# ShieldKL25zG18.net
KiCad netlist of a schematic drawn in Altium Designer
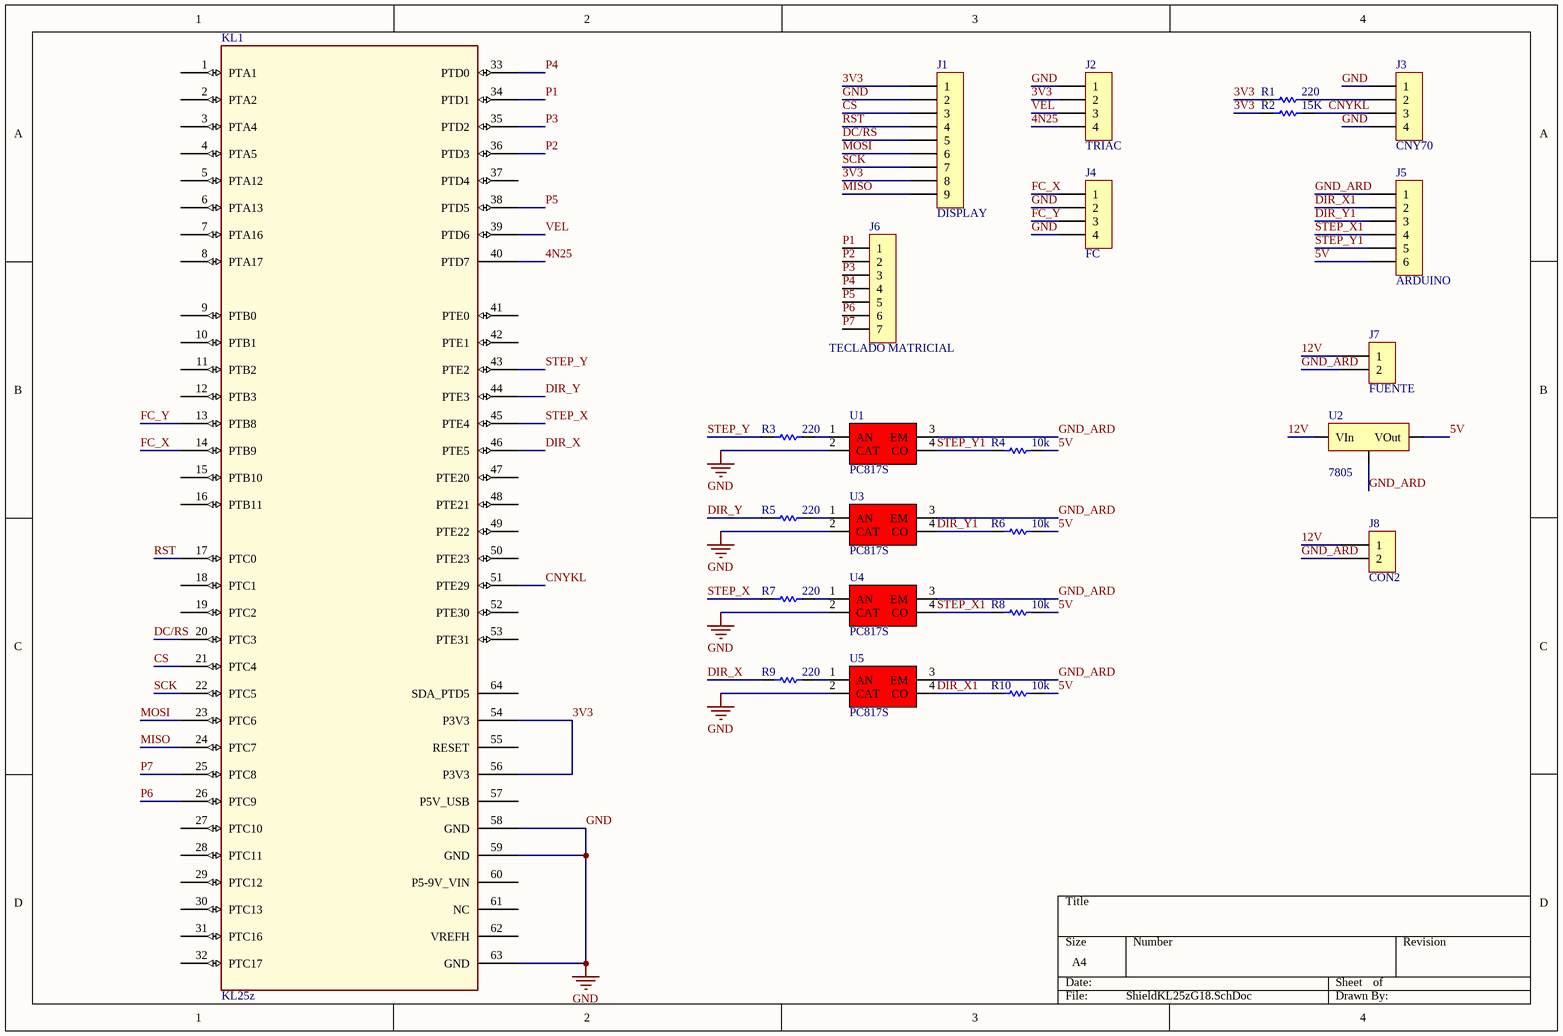
[diagram p0: ShieldKL25zG18.SchDoc]

(export (version "E")
  (design (tool "Eeschema 10.0.6"))
  (components
    (comp (ref "J1") (value "DISPLAY") (footprint "SIP9") (libsource (lib "LIBEBAL") (part "CON9")))
    (comp (ref "J2") (value "TRIAC") (footprint "SIP4") (libsource (lib "ShieldKL25zG18") (part "CON4")))
    (comp (ref "J3") (value "CNY70") (footprint "SIP4") (libsource (lib "Schlib1") (part "CON4")))
    (comp (ref "J4") (value "FC") (footprint "SIP4") (libsource (lib "ShieldKL25zG18") (part "CON4")))
    (comp (ref "J5") (value "ARDUINO") (footprint "SIP6") (libsource (lib "5A_BRULA,Tomas") (part "CON6")))
    (comp (ref "J6")
      (value "TECLADO MATRICIAL")
      (footprint "SIP7")
      (libsource (lib "5A_BRULA,Tomas") (part "CON7"))
    )
    (comp (ref "J7") (value "FUENTE") (footprint "BORNERA2") (libsource (lib "LIBEBAL") (part "BORNERA 2")))
    (comp (ref "J8") (value "CON2") (footprint "SIP2") (libsource (lib "5A_BRULA,Tomas") (part "CON2")))
    (comp (ref "KL1")
      (value "KL25z")
      (footprint "Freedom KL25Z Headerarray")
      (libsource (lib "ShieldKL25zG18") (part "KL25z"))
    )
    (comp (ref "R1") (value "220") (footprint "0805") (libsource (lib "5A_BRULA,Tomas") (part "RES")))
    (comp (ref "R2") (value "15K") (footprint "0805") (libsource (lib "LIBEBAL") (part "RES")))
    (comp (ref "R3") (value "220") (footprint "0805") (libsource (lib "5A_BRULA,Tomas") (part "RES")))
    (comp (ref "R4") (value "10k") (footprint "0805") (libsource (lib "5A_BRULA,Tomas") (part "RES")))
    (comp (ref "R5") (value "220") (footprint "0805") (libsource (lib "5A_BRULA,Tomas") (part "RES")))
    (comp (ref "R6") (value "10k") (footprint "0805") (libsource (lib "5A_BRULA,Tomas") (part "RES")))
    (comp (ref "R7") (value "220") (footprint "0805") (libsource (lib "5A_BRULA,Tomas") (part "RES")))
    (comp (ref "R8") (value "10k") (footprint "0805") (libsource (lib "5A_BRULA,Tomas") (part "RES")))
    (comp (ref "R9") (value "220") (footprint "0805") (libsource (lib "5A_BRULA,Tomas") (part "RES")))
    (comp (ref "R10") (value "10k") (footprint "0805") (libsource (lib "5A_BRULA,Tomas") (part "RES")))
    (comp (ref "U1")
      (value "PC817S")
      (footprint "OPTO_SMD")
      (libsource (lib "5A_BRULA,Tomas") (part "OPTO_SMD"))
    )
    (comp (ref "U2")
      (value "7805")
      (footprint "TO-220 V")
      (description "REGULDOR POSITIVO")
      (libsource (lib "LIBEBAL") (part "78XX"))
    )
    (comp (ref "U3")
      (value "PC817S")
      (footprint "OPTO_SMD")
      (libsource (lib "5A_BRULA,Tomas") (part "OPTO_SMD"))
    )
    (comp (ref "U4")
      (value "PC817S")
      (footprint "OPTO_SMD")
      (libsource (lib "5A_BRULA,Tomas") (part "OPTO_SMD"))
    )
    (comp (ref "U5")
      (value "PC817S")
      (footprint "OPTO_SMD")
      (libsource (lib "5A_BRULA,Tomas") (part "OPTO_SMD"))
    )
  )
  (nets
    (net (code "1") (name "/3V3") (class "Default")
      (node (ref "J1") (pin "1") (pinfunction "1_1") (pintype "passive"))
      (node (ref "J1") (pin "8") (pinfunction "8_8") (pintype "passive"))
      (node (ref "J2") (pin "2") (pinfunction "2_2") (pintype "passive"))
      (node (ref "KL1") (pin "54") (pinfunction "P3V3_54") (pintype "power_in"))
      (node (ref "KL1") (pin "56") (pinfunction "P3V3_56") (pintype "power_in"))
      (node (ref "R1") (pin "1") (pinfunction "1_1") (pintype "passive"))
      (node (ref "R2") (pin "2") (pinfunction "2_2") (pintype "passive"))
    )
    (net (code "2") (name "/4N25") (class "Default")
      (node (ref "J2") (pin "4") (pinfunction "4_4") (pintype "passive"))
      (node (ref "KL1") (pin "40") (pinfunction "PTD7_40") (pintype "passive"))
    )
    (net (code "3") (name "/5V") (class "Default")
      (node (ref "J5") (pin "6") (pinfunction "6_6") (pintype "passive"))
      (node (ref "R10") (pin "2") (pinfunction "2_2") (pintype "passive"))
      (node (ref "R4") (pin "2") (pinfunction "2_2") (pintype "passive"))
      (node (ref "R6") (pin "2") (pinfunction "2_2") (pintype "passive"))
      (node (ref "R8") (pin "2") (pinfunction "2_2") (pintype "passive"))
      (node (ref "U2") (pin "3") (pinfunction "VOut_3") (pintype "passive"))
    )
    (net (code "4") (name "/12V") (class "Default")
      (node (ref "J7") (pin "1") (pinfunction "1_1") (pintype "passive"))
      (node (ref "J8") (pin "1") (pinfunction "1_1") (pintype "passive"))
      (node (ref "U2") (pin "1") (pinfunction "VIn_1") (pintype "passive"))
    )
    (net (code "6") (name "/CNYKL") (class "Default")
      (node (ref "J3") (pin "3") (pinfunction "3_3") (pintype "passive"))
      (node (ref "KL1") (pin "51") (pinfunction "PTE29_51") (pintype "bidirectional"))
      (node (ref "R2") (pin "1") (pinfunction "1_1") (pintype "passive"))
    )
    (net (code "7") (name "/CS") (class "Default")
      (node (ref "J1") (pin "3") (pinfunction "3_3") (pintype "passive"))
      (node (ref "KL1") (pin "21") (pinfunction "PTC4_21") (pintype "bidirectional"))
    )
    (net (code "8") (name "/DC{slash}RS") (class "Default")
      (node (ref "J1") (pin "5") (pinfunction "5_5") (pintype "passive"))
      (node (ref "KL1") (pin "20") (pinfunction "PTC3_20") (pintype "bidirectional"))
    )
    (net (code "9") (name "/DIR_X") (class "Default")
      (node (ref "KL1") (pin "46") (pinfunction "PTE5_46") (pintype "bidirectional"))
      (node (ref "R9") (pin "1") (pinfunction "1_1") (pintype "passive"))
    )
    (net (code "10") (name "/DIR_X1") (class "Default")
      (node (ref "J5") (pin "2") (pinfunction "2_2") (pintype "passive"))
      (node (ref "R10") (pin "1") (pinfunction "1_1") (pintype "passive"))
      (node (ref "U5") (pin "4") (pinfunction "CO_4") (pintype "passive"))
    )
    (net (code "11") (name "/DIR_Y") (class "Default")
      (node (ref "KL1") (pin "44") (pinfunction "PTE3_44") (pintype "bidirectional"))
      (node (ref "R5") (pin "1") (pinfunction "1_1") (pintype "passive"))
    )
    (net (code "12") (name "/DIR_Y1") (class "Default")
      (node (ref "J5") (pin "3") (pinfunction "3_3") (pintype "passive"))
      (node (ref "R6") (pin "1") (pinfunction "1_1") (pintype "passive"))
      (node (ref "U3") (pin "4") (pinfunction "CO_4") (pintype "passive"))
    )
    (net (code "13") (name "/FC_X") (class "Default")
      (node (ref "J4") (pin "1") (pinfunction "1_1") (pintype "passive"))
      (node (ref "KL1") (pin "14") (pinfunction "PTB9_14") (pintype "bidirectional"))
    )
    (net (code "14") (name "/FC_Y") (class "Default")
      (node (ref "J4") (pin "3") (pinfunction "3_3") (pintype "passive"))
      (node (ref "KL1") (pin "13") (pinfunction "PTB8_13") (pintype "bidirectional"))
    )
    (net (code "15") (name "/GND_ARD") (class "Default")
      (node (ref "J5") (pin "1") (pinfunction "1_1") (pintype "passive"))
      (node (ref "J7") (pin "2") (pinfunction "2_2") (pintype "passive"))
      (node (ref "J8") (pin "2") (pinfunction "2_2") (pintype "passive"))
      (node (ref "U1") (pin "3") (pinfunction "EM_3") (pintype "passive"))
      (node (ref "U2") (pin "2") (pinfunction "GND_2") (pintype "passive"))
      (node (ref "U3") (pin "3") (pinfunction "EM_3") (pintype "passive"))
      (node (ref "U4") (pin "3") (pinfunction "EM_3") (pintype "passive"))
      (node (ref "U5") (pin "3") (pinfunction "EM_3") (pintype "passive"))
    )
    (net (code "16") (name "/MISO") (class "Default")
      (node (ref "J1") (pin "9") (pinfunction "9_9") (pintype "passive"))
      (node (ref "KL1") (pin "24") (pinfunction "PTC7_24") (pintype "bidirectional"))
    )
    (net (code "17") (name "/MOSI") (class "Default")
      (node (ref "J1") (pin "6") (pinfunction "6_6") (pintype "passive"))
      (node (ref "KL1") (pin "23") (pinfunction "PTC6_23") (pintype "bidirectional"))
    )
    (net (code "18") (name "/P1") (class "Default")
      (node (ref "J6") (pin "1") (pinfunction "1_1") (pintype "passive"))
      (node (ref "KL1") (pin "34") (pinfunction "PTD1_34") (pintype "bidirectional"))
    )
    (net (code "19") (name "/P2") (class "Default")
      (node (ref "J6") (pin "2") (pinfunction "2_2") (pintype "passive"))
      (node (ref "KL1") (pin "36") (pinfunction "PTD3_36") (pintype "bidirectional"))
    )
    (net (code "20") (name "/P3") (class "Default")
      (node (ref "J6") (pin "3") (pinfunction "3_3") (pintype "passive"))
      (node (ref "KL1") (pin "35") (pinfunction "PTD2_35") (pintype "bidirectional"))
    )
    (net (code "21") (name "/P4") (class "Default")
      (node (ref "J6") (pin "4") (pinfunction "4_4") (pintype "passive"))
      (node (ref "KL1") (pin "33") (pinfunction "PTD0_33") (pintype "bidirectional"))
    )
    (net (code "22") (name "/P5") (class "Default")
      (node (ref "J6") (pin "5") (pinfunction "5_5") (pintype "passive"))
      (node (ref "KL1") (pin "38") (pinfunction "PTD5_38") (pintype "bidirectional"))
    )
    (net (code "23") (name "/P6") (class "Default")
      (node (ref "J6") (pin "6") (pinfunction "6_6") (pintype "passive"))
      (node (ref "KL1") (pin "26") (pinfunction "PTC9_26") (pintype "bidirectional"))
    )
    (net (code "24") (name "/P7") (class "Default")
      (node (ref "J6") (pin "7") (pinfunction "7_7") (pintype "passive"))
      (node (ref "KL1") (pin "25") (pinfunction "PTC8_25") (pintype "bidirectional"))
    )
    (net (code "25") (name "/RST") (class "Default")
      (node (ref "J1") (pin "4") (pinfunction "4_4") (pintype "passive"))
      (node (ref "KL1") (pin "17") (pinfunction "PTC0_17") (pintype "bidirectional"))
    )
    (net (code "26") (name "/SCK") (class "Default")
      (node (ref "J1") (pin "7") (pinfunction "7_7") (pintype "passive"))
      (node (ref "KL1") (pin "22") (pinfunction "PTC5_22") (pintype "bidirectional"))
    )
    (net (code "27") (name "/STEP_X") (class "Default")
      (node (ref "KL1") (pin "45") (pinfunction "PTE4_45") (pintype "bidirectional"))
      (node (ref "R7") (pin "1") (pinfunction "1_1") (pintype "passive"))
    )
    (net (code "28") (name "/STEP_X1") (class "Default")
      (node (ref "J5") (pin "4") (pinfunction "4_4") (pintype "passive"))
      (node (ref "R8") (pin "1") (pinfunction "1_1") (pintype "passive"))
      (node (ref "U4") (pin "4") (pinfunction "CO_4") (pintype "passive"))
    )
    (net (code "29") (name "/STEP_Y") (class "Default")
      (node (ref "KL1") (pin "43") (pinfunction "PTE2_43") (pintype "bidirectional"))
      (node (ref "R3") (pin "1") (pinfunction "1_1") (pintype "passive"))
    )
    (net (code "30") (name "/STEP_Y1") (class "Default")
      (node (ref "J5") (pin "5") (pinfunction "5_5") (pintype "passive"))
      (node (ref "R4") (pin "1") (pinfunction "1_1") (pintype "passive"))
      (node (ref "U1") (pin "4") (pinfunction "CO_4") (pintype "passive"))
    )
    (net (code "31") (name "/VEL") (class "Default")
      (node (ref "J2") (pin "3") (pinfunction "3_3") (pintype "passive"))
      (node (ref "KL1") (pin "39") (pinfunction "PTD6_39") (pintype "bidirectional"))
    )
    (net (code "32") (name "GND") (class "Default")
      (node (ref "J1") (pin "2") (pinfunction "2_2") (pintype "passive"))
      (node (ref "J2") (pin "1") (pinfunction "1_1") (pintype "passive"))
      (node (ref "J3") (pin "1") (pinfunction "1_1") (pintype "passive"))
      (node (ref "J3") (pin "4") (pinfunction "4_4") (pintype "passive"))
      (node (ref "J4") (pin "2") (pinfunction "2_2") (pintype "passive"))
      (node (ref "J4") (pin "4") (pinfunction "4_4") (pintype "passive"))
      (node (ref "KL1") (pin "58") (pinfunction "GND_58") (pintype "power_in"))
      (node (ref "KL1") (pin "59") (pinfunction "GND_59") (pintype "power_in"))
      (node (ref "KL1") (pin "63") (pinfunction "GND_63") (pintype "power_in"))
      (node (ref "U1") (pin "2") (pinfunction "CAT_2") (pintype "passive"))
      (node (ref "U3") (pin "2") (pinfunction "CAT_2") (pintype "passive"))
      (node (ref "U4") (pin "2") (pinfunction "CAT_2") (pintype "passive"))
      (node (ref "U5") (pin "2") (pinfunction "CAT_2") (pintype "passive"))
    )
    (net (code "33") (name "Net-(J3-Pad2)") (class "Default")
      (node (ref "J3") (pin "2") (pinfunction "2_2") (pintype "passive"))
      (node (ref "R1") (pin "2") (pinfunction "2_2") (pintype "passive"))
    )
    (net (code "34") (name "Net-(U1-AN)") (class "Default")
      (node (ref "R3") (pin "2") (pinfunction "2_2") (pintype "passive"))
      (node (ref "U1") (pin "1") (pinfunction "AN_1") (pintype "passive"))
    )
    (net (code "35") (name "Net-(U3-AN)") (class "Default")
      (node (ref "R5") (pin "2") (pinfunction "2_2") (pintype "passive"))
      (node (ref "U3") (pin "1") (pinfunction "AN_1") (pintype "passive"))
    )
    (net (code "36") (name "Net-(U4-AN)") (class "Default")
      (node (ref "R7") (pin "2") (pinfunction "2_2") (pintype "passive"))
      (node (ref "U4") (pin "1") (pinfunction "AN_1") (pintype "passive"))
    )
    (net (code "37") (name "Net-(U5-AN)") (class "Default")
      (node (ref "R9") (pin "2") (pinfunction "2_2") (pintype "passive"))
      (node (ref "U5") (pin "1") (pinfunction "AN_1") (pintype "passive"))
    )
    (net (code "38") (name "unconnected-(KL1-NC-Pad61)") (class "Default")
      (node (ref "KL1") (pin "61") (pinfunction "NC_61") (pintype "passive"))
    )
    (net (code "39") (name "unconnected-(KL1-P5-9V_VIN-Pad60)") (class "Default")
      (node (ref "KL1") (pin "60") (pinfunction "P5-9V_VIN_60") (pintype "passive"))
    )
    (net (code "40") (name "unconnected-(KL1-P5V_USB-Pad57)") (class "Default")
      (node (ref "KL1") (pin "57") (pinfunction "P5V_USB_57") (pintype "passive"))
    )
    (net (code "41") (name "unconnected-(KL1-PTA1-Pad1)") (class "Default")
      (node (ref "KL1") (pin "1") (pinfunction "PTA1_1") (pintype "bidirectional"))
    )
    (net (code "42") (name "unconnected-(KL1-PTA2-Pad2)") (class "Default")
      (node (ref "KL1") (pin "2") (pinfunction "PTA2_2") (pintype "bidirectional"))
    )
    (net (code "43") (name "unconnected-(KL1-PTA4-Pad3)") (class "Default")
      (node (ref "KL1") (pin "3") (pinfunction "PTA4_3") (pintype "bidirectional"))
    )
    (net (code "44") (name "unconnected-(KL1-PTA5-Pad4)") (class "Default")
      (node (ref "KL1") (pin "4") (pinfunction "PTA5_4") (pintype "bidirectional"))
    )
    (net (code "45") (name "unconnected-(KL1-PTA12-Pad5)") (class "Default")
      (node (ref "KL1") (pin "5") (pinfunction "PTA12_5") (pintype "bidirectional"))
    )
    (net (code "46") (name "unconnected-(KL1-PTA13-Pad6)") (class "Default")
      (node (ref "KL1") (pin "6") (pinfunction "PTA13_6") (pintype "bidirectional"))
    )
    (net (code "47") (name "unconnected-(KL1-PTA16-Pad7)") (class "Default")
      (node (ref "KL1") (pin "7") (pinfunction "PTA16_7") (pintype "bidirectional"))
    )
    (net (code "48") (name "unconnected-(KL1-PTA17-Pad8)") (class "Default")
      (node (ref "KL1") (pin "8") (pinfunction "PTA17_8") (pintype "bidirectional"))
    )
    (net (code "49") (name "unconnected-(KL1-PTB0-Pad9)") (class "Default")
      (node (ref "KL1") (pin "9") (pinfunction "PTB0_9") (pintype "bidirectional"))
    )
    (net (code "50") (name "unconnected-(KL1-PTB1-Pad10)") (class "Default")
      (node (ref "KL1") (pin "10") (pinfunction "PTB1_10") (pintype "bidirectional"))
    )
    (net (code "51") (name "unconnected-(KL1-PTB2-Pad11)") (class "Default")
      (node (ref "KL1") (pin "11") (pinfunction "PTB2_11") (pintype "bidirectional"))
    )
    (net (code "52") (name "unconnected-(KL1-PTB3-Pad12)") (class "Default")
      (node (ref "KL1") (pin "12") (pinfunction "PTB3_12") (pintype "bidirectional"))
    )
    (net (code "53") (name "unconnected-(KL1-PTB10-Pad15)") (class "Default")
      (node (ref "KL1") (pin "15") (pinfunction "PTB10_15") (pintype "bidirectional"))
    )
    (net (code "54") (name "unconnected-(KL1-PTB11-Pad16)") (class "Default")
      (node (ref "KL1") (pin "16") (pinfunction "PTB11_16") (pintype "bidirectional"))
    )
    (net (code "55") (name "unconnected-(KL1-PTC1-Pad18)") (class "Default")
      (node (ref "KL1") (pin "18") (pinfunction "PTC1_18") (pintype "bidirectional"))
    )
    (net (code "56") (name "unconnected-(KL1-PTC2-Pad19)") (class "Default")
      (node (ref "KL1") (pin "19") (pinfunction "PTC2_19") (pintype "bidirectional"))
    )
    (net (code "57") (name "unconnected-(KL1-PTC10-Pad27)") (class "Default")
      (node (ref "KL1") (pin "27") (pinfunction "PTC10_27") (pintype "bidirectional"))
    )
    (net (code "58") (name "unconnected-(KL1-PTC11-Pad28)") (class "Default")
      (node (ref "KL1") (pin "28") (pinfunction "PTC11_28") (pintype "bidirectional"))
    )
    (net (code "59") (name "unconnected-(KL1-PTC12-Pad29)") (class "Default")
      (node (ref "KL1") (pin "29") (pinfunction "PTC12_29") (pintype "bidirectional"))
    )
    (net (code "60") (name "unconnected-(KL1-PTC13-Pad30)") (class "Default")
      (node (ref "KL1") (pin "30") (pinfunction "PTC13_30") (pintype "bidirectional"))
    )
    (net (code "61") (name "unconnected-(KL1-PTC16-Pad31)") (class "Default")
      (node (ref "KL1") (pin "31") (pinfunction "PTC16_31") (pintype "bidirectional"))
    )
    (net (code "62") (name "unconnected-(KL1-PTC17-Pad32)") (class "Default")
      (node (ref "KL1") (pin "32") (pinfunction "PTC17_32") (pintype "bidirectional"))
    )
    (net (code "63") (name "unconnected-(KL1-PTD4-Pad37)") (class "Default")
      (node (ref "KL1") (pin "37") (pinfunction "PTD4_37") (pintype "bidirectional"))
    )
    (net (code "64") (name "unconnected-(KL1-PTE0-Pad41)") (class "Default")
      (node (ref "KL1") (pin "41") (pinfunction "PTE0_41") (pintype "bidirectional"))
    )
    (net (code "65") (name "unconnected-(KL1-PTE1-Pad42)") (class "Default")
      (node (ref "KL1") (pin "42") (pinfunction "PTE1_42") (pintype "bidirectional"))
    )
    (net (code "66") (name "unconnected-(KL1-PTE20-Pad47)") (class "Default")
      (node (ref "KL1") (pin "47") (pinfunction "PTE20_47") (pintype "bidirectional"))
    )
    (net (code "67") (name "unconnected-(KL1-PTE21-Pad48)") (class "Default")
      (node (ref "KL1") (pin "48") (pinfunction "PTE21_48") (pintype "bidirectional"))
    )
    (net (code "68") (name "unconnected-(KL1-PTE22-Pad49)") (class "Default")
      (node (ref "KL1") (pin "49") (pinfunction "PTE22_49") (pintype "bidirectional"))
    )
    (net (code "69") (name "unconnected-(KL1-PTE23-Pad50)") (class "Default")
      (node (ref "KL1") (pin "50") (pinfunction "PTE23_50") (pintype "bidirectional"))
    )
    (net (code "70") (name "unconnected-(KL1-PTE30-Pad52)") (class "Default")
      (node (ref "KL1") (pin "52") (pinfunction "PTE30_52") (pintype "bidirectional"))
    )
    (net (code "71") (name "unconnected-(KL1-PTE31-Pad53)") (class "Default")
      (node (ref "KL1") (pin "53") (pinfunction "PTE31_53") (pintype "bidirectional"))
    )
    (net (code "72") (name "unconnected-(KL1-RESET-Pad55)") (class "Default")
      (node (ref "KL1") (pin "55") (pinfunction "RESET_55") (pintype "passive"))
    )
    (net (code "73") (name "unconnected-(KL1-SDA_PTD5-Pad64)") (class "Default")
      (node (ref "KL1") (pin "64") (pinfunction "SDA_PTD5_64") (pintype "passive"))
    )
    (net (code "74") (name "unconnected-(KL1-VREFH-Pad62)") (class "Default")
      (node (ref "KL1") (pin "62") (pinfunction "VREFH_62") (pintype "passive"))
    )
  )
)
